# 12__MOT_tCONNECTOR.net
KiCad netlist of a schematic drawn in Altium Designer
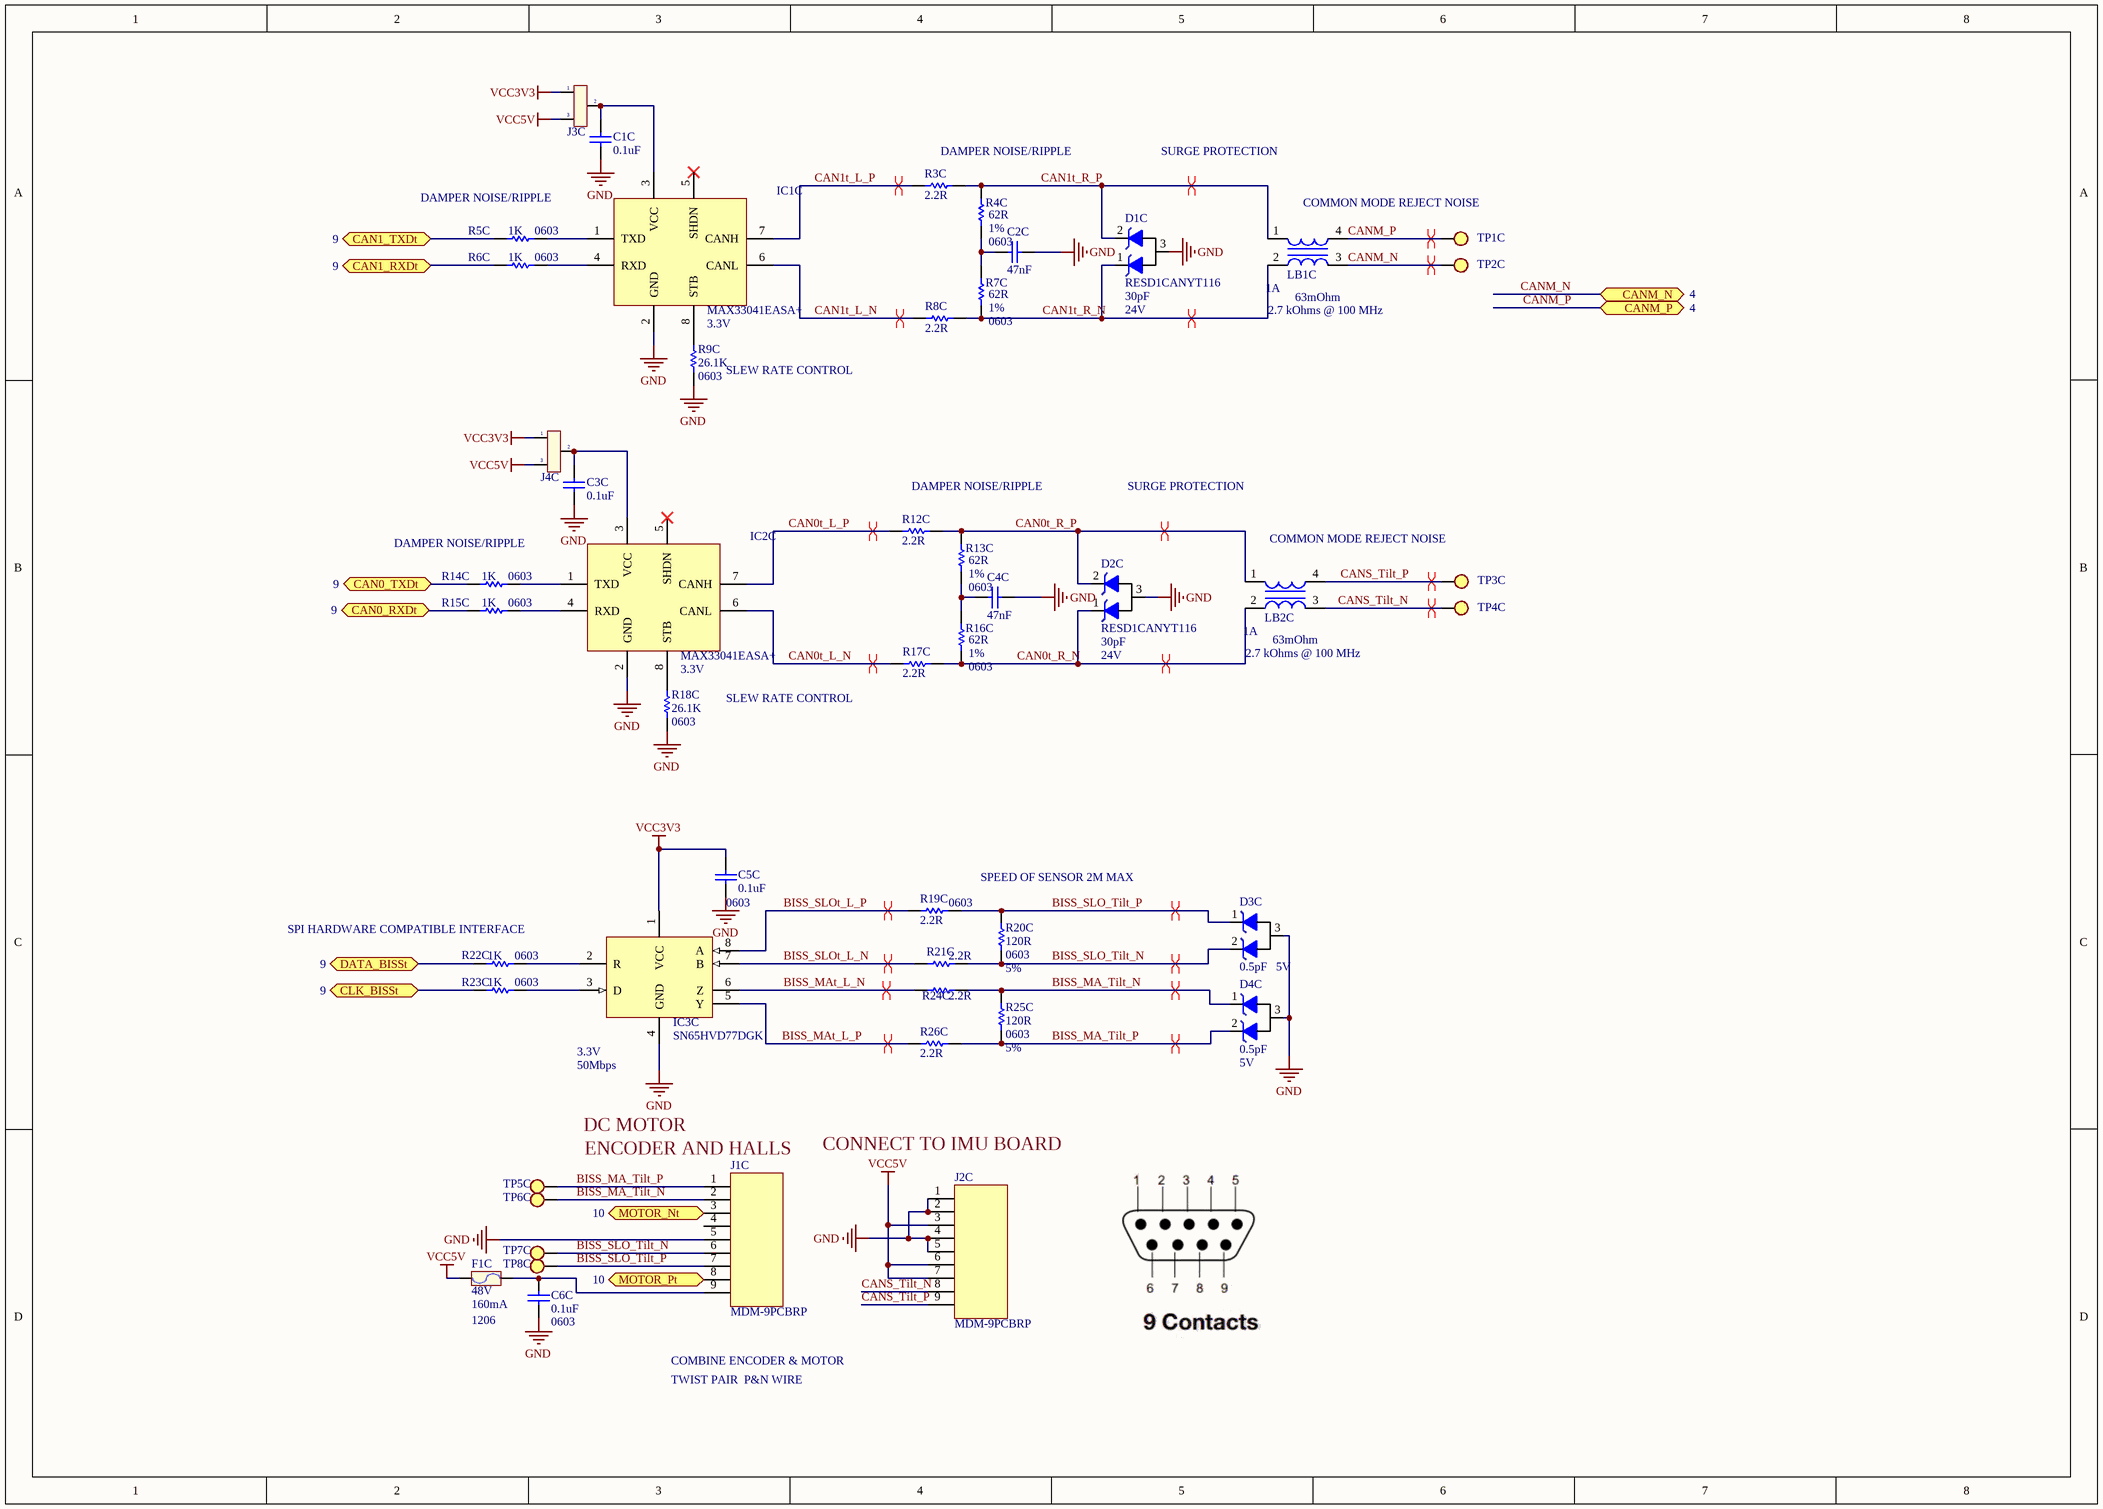
[diagram p0: [12]_MOT_tCONNECTOR.SchDoc]

(export (version "E")
  (design (tool "Eeschema 10.0.6"))
  (components
    (comp (ref "C1C")
      (value "0.1uF")
      (footprint "CAP 0603")
      (description "CAP-CER,SMD;0.1UF,10%,50V,X7R,0603")
      (fields (field (name "VOLTAGE") "50V") (field (name "TOLERANCE") "±10%"))
      (libsource (lib "Slider") (part "Cap"))
    )
    (comp (ref "C2C")
      (value "47nF")
      (footprint "CAP 0603")
      (description "CAP-CER,SMD; 47nF,10%,50V,X7R,0603")
      (fields (field (name "VOLTAGE") "50V") (field (name "TOLERANCE") "±10%"))
      (libsource (lib "Slider") (part "Cap"))
    )
    (comp (ref "C3C")
      (value "0.1uF")
      (footprint "CAP 0603")
      (description "CAP-CER,SMD;0.1UF,10%,50V,X7R,0603")
      (fields (field (name "VOLTAGE") "50V") (field (name "TOLERANCE") "±10%"))
      (libsource (lib "Slider") (part "Cap"))
    )
    (comp (ref "C4C")
      (value "47nF")
      (footprint "CAP 0603")
      (description "CAP-CER,SMD; 47nF,10%,50V,X7R,0603")
      (fields (field (name "VOLTAGE") "50V") (field (name "TOLERANCE") "±10%"))
      (libsource (lib "Slider") (part "Cap"))
    )
    (comp (ref "C5C")
      (value "0.1uF")
      (footprint "0603")
      (description "CAP-CER,SMD;0.1UF,10%,50V,X7R,0603")
      (fields (field (name "VOLTAGE") "50V") (field (name "TOLERANCE") "±10%"))
      (libsource (lib "Slider") (part "Cap"))
    )
    (comp (ref "C6C")
      (value "0.1uF")
      (footprint "0603")
      (description "CAP-CER,SMD;0.1UF,10%,50V,X7R,0603")
      (fields (field (name "VOLTAGE") "50V") (field (name "TOLERANCE") "±10%"))
      (libsource (lib "Slider") (part "Cap"))
    )
    (comp (ref "D1C")
      (value "RESD1CANYT116")
      (footprint "SOT-23-3")
      (description "TVS DIODE 24VWM 50VC SOT23-")
      (fields
        (field (name "POWER") "230W")
        (field (name "CAPACITANCE") "30pF")
        (field (name "VOLTAGE") "24V")
      )
      (libsource (lib "") (part "TVS_DUAL_SIGNAL_5V_SOT23_1"))
    )
    (comp (ref "D2C")
      (value "RESD1CANYT116")
      (footprint "SOT-23-3")
      (description "TVS DIODE 24VWM 50VC SOT23-")
      (fields
        (field (name "POWER") "230W")
        (field (name "CAPACITANCE") "30pF")
        (field (name "VOLTAGE") "24V")
      )
      (libsource (lib "") (part "TVS_DUAL_SIGNAL_5V_SOT23_1"))
    )
    (comp (ref "D3C")
      (value "ESDR0502BT1G")
      (footprint "SOT-416")
      (description "5V, ESD PROTECTION DEVICES, SOT-23")
      (fields
        (field (name "MANUFACTURER2_PART#") "DF3D6.8MS,LF")
        (field (name "POWER") "320W")
        (field (name "CAPACITANCE") "0.5pF")
        (field (name "VOLTAGE") "5V")
      )
      (libsource (lib "My Library") (part "TVS_DUAL_SIGNAL_5V_SOT23"))
    )
    (comp (ref "D4C")
      (value "ESDR0502BT1G")
      (footprint "SOT-416")
      (description "5V, ESD PROTECTION DEVICES, SOT-23")
      (fields
        (field (name "MANUFACTURER2_PART#") "DF3D6.8MS,LF")
        (field (name "POWER") "320W")
        (field (name "CAPACITANCE") "0.5pF")
        (field (name "VOLTAGE") "5V")
      )
      (libsource (lib "My Library") (part "TVS_DUAL_SIGNAL_5V_SOT23"))
    )
    (comp (ref "F1C")
      (value "0ZCG0014FF2C")
      (footprint "RES 1206")
      (description "PTC RESET FUSE 48V 160MA 1206")
      (fields
        (field (name "MANUFACTURER1_PART#") "0ZCJ0016FF2E")
        (field (name "MANUFACTURER2_PART#") "CLA1684")
        (field (name "VOLTAGE - RATED") "48V")
        (field (name "PACKAGE / CASE") "1206")
        (field (name "CURRENT RATING (AMPS)") "160mA")
      )
      (libsource (lib "K Shematic") (part "0875.800MXEP"))
    )
    (comp (ref "IC1C")
      (value "MAX33041EASA+")
      (footprint "8-SOIC")
      (description "IC CAN TXRX 3.3V 2MBPS SOIC")
      (fields (field (name "MANUFACTURER PART NUMBER") "MAX33041EASA+") (field (name "VOLTAGE") "3.3V"))
      (libsource (lib "OE Seeker-IsolatedPower") (part "IC;IC CAN TRANSEIVER HS,8SOIC,-40TO150°C,TJA1042T/3,118"))
    )
    (comp (ref "IC2C")
      (value "MAX33041EASA+")
      (footprint "8-SOIC")
      (description "IC CAN TXRX 3.3V 2MBPS SOIC")
      (fields (field (name "MANUFACTURER PART NUMBER") "MAX33041EASA+") (field (name "VOLTAGE") "3.3V"))
      (libsource (lib "OE Seeker-IsolatedPower") (part "IC;IC CAN TRANSEIVER HS,8SOIC,-40TO150°C,TJA1042T/3,118"))
    )
    (comp (ref "IC3C")
      (value "IC;IC TRANSCEIVER FULL 1/1 8SOIC,8-SOIC,-40TO 85°C,SN65HVD77DR")
      (footprint "8-VSSOP")
      (description "IC TRANSCEIVER FULL 1/1 8VSSOP")
      (fields
        (field (name "MANUFACTURER") "TI")
        (field (name "MANUFACTURER PART NUMBER") "SN65HVD77DGK")
        (field (name "MANUFACTURER1_PART#") "SN65HVD77DGK")
        (field (name "VOLTAGE") "3.3V")
        (field (name "SPEED") "50Mbps")
      )
      (libsource (lib "DRIVER MOTION TILT_NEW") (part "IC;IC TRANSCEIVER FULL 1/1 8SOIC,8-SOIC,-40TO 85°C,SN65HVD77DR"))
    )
    (comp (ref "J1C")
      (value "CONN-DIP;CONN MICRO-D PLUG 9POS R/A SLDR,M,MDM-9PCBRP")
      (footprint "MDM-9PCBRP")
      (description "CONN MICRO-D PLUG 9POS R/A SLDR")
      (fields
        (field (name "MANUFACTURER") "ITT CANNON, LLC")
        (field (name "MANUFACTURER PART NUMBER") "MDM-9PCBRP")
        (field (name "MANUFACTURER1_PART#") "MDM-9PCBRP")
      )
      (libsource (lib "DRIVER MOTION PAN_NEW") (part "CONN-DIP;CONN MICRO-D PLUG 9POS R/A SLDR,M,MDM-9PCBRP"))
    )
    (comp (ref "J2C")
      (value "CONN-DIP;CONN MICRO-D PLUG 9POS R/A SLDR,M,MDM-9PCBRP")
      (footprint "MDM-9PCBRP")
      (description "CONN MICRO-D PLUG 9POS R/A SLDR")
      (fields
        (field (name "MANUFACTURER") "ITT CANNON, LLC")
        (field (name "MANUFACTURER PART NUMBER") "MDM-9PCBRP")
        (field (name "MANUFACTURER1_PART#") "MDM-9PCBRP")
      )
      (libsource (lib "IMU_NEW") (part "CONN-DIP;CONN MICRO-D PLUG 9POS R/A SLDR,M,MDM-9PCBRP"))
    )
    (comp (ref "J3C")
      (value "JP 2-1")
      (footprint "JP3")
      (description "Jumper 2-1")
      (libsource (lib "ThanhSchematicLib") (part "JP 2-1"))
    )
    (comp (ref "J4C")
      (value "JP 2-1")
      (footprint "JP3")
      (description "Jumper 2-1")
      (libsource (lib "ThanhSchematicLib") (part "JP 2-1"))
    )
    (comp (ref "LB1C")
      (value "MCM-7060M-272-RU")
      (footprint "MCM-7060M")
      (description "CMC 1A 2LN 2.7KOHM SMD")
      (fields
        (field (name "CURRENT") "1A")
        (field (name "IMPEDANCE") "2.7 kOhms @ 100 MHz")
        (field (name "DCR") "63mOhm")
      )
      (libsource (lib "OE Seeker-IsolatedPower") (part "CHOKE-SMD;90OHM@100MHz,0.15A,5V,DLP11SA900HL2L"))
    )
    (comp (ref "LB2C")
      (value "MCM-7060M-272-RU")
      (footprint "MCM-7060M")
      (description "CMC 1A 2LN 2.7KOHM SMD")
      (fields
        (field (name "CURRENT") "1A")
        (field (name "IMPEDANCE") "2.7 kOhms @ 100 MHz")
        (field (name "DCR") "63mOhm")
      )
      (libsource (lib "OE Seeker-IsolatedPower") (part "CHOKE-SMD;90OHM@100MHz,0.15A,5V,DLP11SA900HL2L"))
    )
    (comp (ref "R3C")
      (value "2.2R")
      (footprint "res 0603")
      (description "RES SMD 2.2 OHM 5% 1/10W 0603")
      (fields
        (field (name "MANUFACTURER1_PART#") "RC0603JR-072R2L")
        (field (name "MANUFACTURER2_PART#") "RMCF0603JT2R20")
      )
      (libsource (lib "Full") (part "Res0.3"))
    )
    (comp (ref "R4C")
      (value "62R")
      (footprint "R0603")
      (description "RES SM 62 OHM 1% 1/10W 0603")
      (fields
        (field (name "MANUFACTURER1_PART#") "RMCF0603FT62R0")
        (field (name "MANUFACTURER2_PART#") "RC0603FR-0762RL")
        (field (name "TOLERANCE") "1%")
        (field (name "PACKAGE") "0603")
      )
      (libsource (lib "OE Seeker-IsolatedPower") (part "RES-SMD;60.4OHM,1%,0402,1/10W"))
    )
    (comp (ref "R5C")
      (value "1K")
      (footprint "res 0603")
      (description "RES SMD,1K OHM,5%,1/10W,0603")
      (fields
        (field (name "MANUFACTURER1_PART#") "RMCF06031K00JNEAC")
        (field (name "MANUFACTURER2_PART#") "R0603J1KTG")
        (field (name "PCB FOOTPRINT") "0603")
      )
      (libsource (lib "Full") (part "Res0.3"))
    )
    (comp (ref "R6C")
      (value "1K")
      (footprint "res 0603")
      (description "RES SMD,1K OHM,5%,1/10W,0603")
      (fields
        (field (name "MANUFACTURER1_PART#") "RMCF06031K00JNEAC")
        (field (name "MANUFACTURER2_PART#") "R0603J1KTG")
        (field (name "PCB FOOTPRINT") "0603")
      )
      (libsource (lib "Full") (part "Res0.3"))
    )
    (comp (ref "R7C")
      (value "62R")
      (footprint "R0603")
      (description "RES SM 62 OHM 1% 1/10W 0603")
      (fields
        (field (name "MANUFACTURER1_PART#") "RMCF0603FT62R0")
        (field (name "MANUFACTURER2_PART#") "RC0603FR-0762RL")
        (field (name "TOLERANCE") "1%")
        (field (name "PACKAGE") "0603")
      )
      (libsource (lib "OE Seeker-IsolatedPower") (part "RES-SMD;60.4OHM,1%,0402,1/10W"))
    )
    (comp (ref "R8C")
      (value "2.2R")
      (footprint "res 0603")
      (description "RES SMD 2.2 OHM 5% 1/10W 0603")
      (fields
        (field (name "MANUFACTURER1_PART#") "RC0603JR-072R2L")
        (field (name "MANUFACTURER2_PART#") "RMCF0603JT2R20")
      )
      (libsource (lib "Full") (part "Res0.3"))
    )
    (comp (ref "R9C")
      (value "26.1K")
      (footprint "R0603")
      (description "RES 26.1K OHM 1% 1/10W 0603")
      (fields
        (field (name "MANUFACTURER1_PART#") "RMCF0603FT26K1")
        (field (name "MANUFACTURER2_PART#") "RC0603FR-0726K1L")
        (field (name "PCB FOOTPRINT") "0603")
      )
      (libsource (lib "altium-import") (part "root_3_Res0.3_"))
    )
    (comp (ref "R12C")
      (value "2.2R")
      (footprint "res 0603")
      (description "RES SMD 2.2 OHM 5% 1/10W 0603")
      (fields
        (field (name "MANUFACTURER1_PART#") "RC0603JR-072R2L")
        (field (name "MANUFACTURER2_PART#") "RMCF0603JT2R20")
      )
      (libsource (lib "Full") (part "Res0.3"))
    )
    (comp (ref "R13C")
      (value "62R")
      (footprint "R0603")
      (description "RES SM 62 OHM 1% 1/10W 0603")
      (fields
        (field (name "MANUFACTURER1_PART#") "RMCF0603FT62R0")
        (field (name "MANUFACTURER2_PART#") "RC0603FR-0762RL")
        (field (name "TOLERANCE") "1%")
        (field (name "PACKAGE") "0603")
      )
      (libsource (lib "OE Seeker-IsolatedPower") (part "RES-SMD;60.4OHM,1%,0402,1/10W"))
    )
    (comp (ref "R14C")
      (value "1K")
      (footprint "res 0603")
      (description "RES SMD,1K OHM,5%,1/10W,0603")
      (fields
        (field (name "MANUFACTURER1_PART#") "RMCF06031K00JNEAC")
        (field (name "MANUFACTURER2_PART#") "R0603J1KTG")
        (field (name "PCB FOOTPRINT") "0603")
      )
      (libsource (lib "Full") (part "Res0.3"))
    )
    (comp (ref "R15C")
      (value "1K")
      (footprint "res 0603")
      (description "RES SMD,1K OHM,5%,1/10W,0603")
      (fields
        (field (name "MANUFACTURER1_PART#") "RMCF06031K00JNEAC")
        (field (name "MANUFACTURER2_PART#") "R0603J1KTG")
        (field (name "PCB FOOTPRINT") "0603")
      )
      (libsource (lib "Full") (part "Res0.3"))
    )
    (comp (ref "R16C")
      (value "62R")
      (footprint "R0603")
      (description "RES SM 62 OHM 1% 1/10W 0603")
      (fields
        (field (name "MANUFACTURER1_PART#") "RMCF0603FT62R0")
        (field (name "MANUFACTURER2_PART#") "RC0603FR-0762RL")
        (field (name "TOLERANCE") "1%")
        (field (name "PACKAGE") "0603")
      )
      (libsource (lib "OE Seeker-IsolatedPower") (part "RES-SMD;60.4OHM,1%,0402,1/10W"))
    )
    (comp (ref "R17C")
      (value "2.2R")
      (footprint "res 0603")
      (description "RES SMD 2.2 OHM 5% 1/10W 0603")
      (fields
        (field (name "MANUFACTURER1_PART#") "RC0603JR-072R2L")
        (field (name "MANUFACTURER2_PART#") "RMCF0603JT2R20")
      )
      (libsource (lib "Full") (part "Res0.3"))
    )
    (comp (ref "R18C")
      (value "26.1K")
      (footprint "R0603")
      (description "RES 26.1K OHM 1% 1/10W 0603")
      (fields
        (field (name "MANUFACTURER1_PART#") "RMCF0603FT26K1")
        (field (name "MANUFACTURER2_PART#") "RC0603FR-0726K1L")
        (field (name "PCB FOOTPRINT") "0603")
      )
      (libsource (lib "altium-import") (part "root_3_Res0.3_"))
    )
    (comp (ref "R19C")
      (value "2.2R")
      (footprint "res 0603")
      (description "RES SMD 2.2 OHM 5% 1/10W 0603")
      (fields
        (field (name "MANUFACTURER1_PART#") "RC0603JR-072R2L")
        (field (name "MANUFACTURER2_PART#") "RMCF0603JT2R20")
        (field (name "PCB FOOTPRINT") "0603")
      )
      (libsource (lib "Full") (part "Res0.3"))
    )
    (comp (ref "R20C")
      (value "120R")
      (footprint "res 0603")
      (description "RES 120 OHM 5% 1/10W 0603")
      (fields
        (field (name "MANUFACTURER1_PART#") "RMCF0603JG120R")
        (field (name "PCB_ FOOTPRINT") "0603")
        (field (name "TOLERANCE") "5%")
      )
      (libsource (lib "thuvien") (part "RES 120 OHM 5% 1/10W 0603"))
    )
    (comp (ref "R21C")
      (value "2.2R")
      (footprint "res 0603")
      (description "RES SMD 2.2 OHM 5% 1/10W 0603")
      (fields
        (field (name "MANUFACTURER1_PART#") "RC0603JR-072R2L")
        (field (name "MANUFACTURER2_PART#") "RMCF0603JT2R20")
      )
      (libsource (lib "Full") (part "Res0.3"))
    )
    (comp (ref "R22C")
      (value "1K")
      (footprint "res 0603")
      (description "RES SMD,1K OHM,5%,1/10W,0603")
      (fields
        (field (name "MANUFACTURER1_PART#") "RMCF06031K00JNEAC")
        (field (name "MANUFACTURER2_PART#") "R0603J1KTG")
        (field (name "PCB FOOTPRINT") "0603")
      )
      (libsource (lib "Full") (part "Res0.3"))
    )
    (comp (ref "R23C")
      (value "1K")
      (footprint "res 0603")
      (description "RES SMD,1K OHM,5%,1/10W,0603")
      (fields
        (field (name "MANUFACTURER1_PART#") "RMCF06031K00JNEAC")
        (field (name "MANUFACTURER2_PART#") "R0603J1KTG")
        (field (name "PCB FOOTPRINT") "0603")
      )
      (libsource (lib "Full") (part "Res0.3"))
    )
    (comp (ref "R24C")
      (value "2.2R")
      (footprint "res 0603")
      (description "RES SMD 2.2 OHM 5% 1/10W 0603")
      (fields
        (field (name "MANUFACTURER1_PART#") "RC0603JR-072R2L")
        (field (name "MANUFACTURER2_PART#") "RMCF0603JT2R20")
      )
      (libsource (lib "Full") (part "Res0.3"))
    )
    (comp (ref "R25C")
      (value "120R")
      (footprint "res 0603")
      (description "RES 120 OHM 5% 1/10W 0603")
      (fields
        (field (name "MANUFACTURER1_PART#") "RMCF0603JG120R")
        (field (name "PCB_ FOOTPRINT") "0603")
        (field (name "TOLERANCE") "5%")
      )
      (libsource (lib "thuvien") (part "RES 120 OHM 5% 1/10W 0603"))
    )
    (comp (ref "R26C")
      (value "2.2R")
      (footprint "res 0603")
      (description "RES SMD 2.2 OHM 5% 1/10W 0603")
      (fields
        (field (name "MANUFACTURER1_PART#") "RC0603JR-072R2L")
        (field (name "MANUFACTURER2_PART#") "RMCF0603JT2R20")
      )
      (libsource (lib "Full") (part "Res0.3"))
    )
    (comp (ref "TP1C")
      (value "TP SMD")
      (footprint "TESTPOINT")
      (description "TEST POINT")
      (libsource (lib "VSM") (part "TP SMD"))
    )
    (comp (ref "TP2C")
      (value "TP SMD")
      (footprint "TESTPOINT")
      (description "TEST POINT")
      (libsource (lib "VSM") (part "TP SMD"))
    )
    (comp (ref "TP3C")
      (value "TP SMD")
      (footprint "TESTPOINT")
      (description "TEST POINT")
      (libsource (lib "VSM") (part "TP SMD"))
    )
    (comp (ref "TP4C")
      (value "TP SMD")
      (footprint "TESTPOINT")
      (description "TEST POINT")
      (libsource (lib "VSM") (part "TP SMD"))
    )
    (comp (ref "TP5C")
      (value "TP SMD")
      (footprint "TESTPOINT")
      (description "TEST POINT")
      (libsource (lib "VSM") (part "TP SMD"))
    )
    (comp (ref "TP6C")
      (value "TP SMD")
      (footprint "TESTPOINT")
      (description "TEST POINT")
      (libsource (lib "VSM") (part "TP SMD"))
    )
    (comp (ref "TP7C")
      (value "TP SMD")
      (footprint "TESTPOINT")
      (description "TEST POINT")
      (libsource (lib "VSM") (part "TP SMD"))
    )
    (comp (ref "TP8C")
      (value "TP SMD")
      (footprint "TESTPOINT")
      (description "TEST POINT")
      (libsource (lib "VSM") (part "TP SMD"))
    )
  )
  (nets
    (net (code "1") (name "/BISS_MA_Tilt_N") (class "Default")
      (node (ref "D4C") (pin "1") (pinfunction "K_1") (pintype "passive"))
      (node (ref "J1C") (pin "2") (pinfunction "2_2") (pintype "passive"))
      (node (ref "R24C") (pin "1") (pinfunction "1_1") (pintype "passive"))
      (node (ref "R25C") (pin "1") (pinfunction "1_1") (pintype "passive"))
      (node (ref "TP6C") (pin "1") (pinfunction "1_1") (pintype "passive"))
    )
    (net (code "2") (name "/BISS_MA_Tilt_P") (class "Default")
      (node (ref "D4C") (pin "2") (pinfunction "K_2") (pintype "passive"))
      (node (ref "J1C") (pin "1") (pinfunction "1_1") (pintype "passive"))
      (node (ref "R25C") (pin "2") (pinfunction "2_2") (pintype "passive"))
      (node (ref "R26C") (pin "1") (pinfunction "1_1") (pintype "passive"))
      (node (ref "TP5C") (pin "1") (pinfunction "1_1") (pintype "passive"))
    )
    (net (code "3") (name "/BISS_MAt_L_N") (class "Default")
      (node (ref "IC3C") (pin "6") (pinfunction "Z_6") (pintype "passive"))
      (node (ref "R24C") (pin "2") (pinfunction "2_2") (pintype "passive"))
    )
    (net (code "4") (name "/BISS_MAt_L_P") (class "Default")
      (node (ref "IC3C") (pin "5") (pinfunction "Y_5") (pintype "passive"))
      (node (ref "R26C") (pin "2") (pinfunction "2_2") (pintype "passive"))
    )
    (net (code "5") (name "/BISS_SLO_Tilt_N") (class "Default")
      (node (ref "D3C") (pin "2") (pinfunction "K_2") (pintype "passive"))
      (node (ref "J1C") (pin "6") (pinfunction "6_6") (pintype "passive"))
      (node (ref "R20C") (pin "2") (pinfunction "2_2") (pintype "passive"))
      (node (ref "R21C") (pin "1") (pinfunction "1_1") (pintype "passive"))
      (node (ref "TP7C") (pin "1") (pinfunction "1_1") (pintype "passive"))
    )
    (net (code "6") (name "/BISS_SLO_Tilt_P") (class "Default")
      (node (ref "D3C") (pin "1") (pinfunction "K_1") (pintype "passive"))
      (node (ref "J1C") (pin "7") (pinfunction "7_7") (pintype "passive"))
      (node (ref "R19C") (pin "1") (pinfunction "1_1") (pintype "passive"))
      (node (ref "R20C") (pin "1") (pinfunction "1_1") (pintype "passive"))
      (node (ref "TP8C") (pin "1") (pinfunction "1_1") (pintype "passive"))
    )
    (net (code "7") (name "/BISS_SLOt_L_N") (class "Default")
      (node (ref "IC3C") (pin "7") (pinfunction "B_7") (pintype "input"))
      (node (ref "R21C") (pin "2") (pinfunction "2_2") (pintype "passive"))
    )
    (net (code "8") (name "/BISS_SLOt_L_P") (class "Default")
      (node (ref "IC3C") (pin "8") (pinfunction "A_8") (pintype "input"))
      (node (ref "R19C") (pin "2") (pinfunction "2_2") (pintype "passive"))
    )
    (net (code "9") (name "/CAN0_RXDt") (class "Default")
      (node (ref "R15C") (pin "2") (pinfunction "2_2") (pintype "passive"))
    )
    (net (code "10") (name "/CAN0_TXDt") (class "Default")
      (node (ref "R14C") (pin "2") (pinfunction "2_2") (pintype "passive"))
    )
    (net (code "11") (name "/CAN0t_L_N") (class "Default")
      (node (ref "IC2C") (pin "6") (pinfunction "CANL_6") (pintype "passive"))
      (node (ref "R17C") (pin "2") (pinfunction "2_2") (pintype "passive"))
    )
    (net (code "12") (name "/CAN0t_L_P") (class "Default")
      (node (ref "IC2C") (pin "7") (pinfunction "CANH_7") (pintype "passive"))
      (node (ref "R12C") (pin "2") (pinfunction "2_2") (pintype "passive"))
    )
    (net (code "13") (name "/CAN0t_R_N") (class "Default")
      (node (ref "D2C") (pin "1") (pinfunction "K_1") (pintype "passive"))
      (node (ref "LB2C") (pin "2") (pinfunction "2_2") (pintype "passive"))
      (node (ref "R16C") (pin "1") (pinfunction "1_1") (pintype "passive"))
      (node (ref "R17C") (pin "1") (pinfunction "1_1") (pintype "passive"))
    )
    (net (code "14") (name "/CAN0t_R_P") (class "Default")
      (node (ref "D2C") (pin "2") (pinfunction "K_2") (pintype "passive"))
      (node (ref "LB2C") (pin "1") (pinfunction "1_1") (pintype "passive"))
      (node (ref "R12C") (pin "1") (pinfunction "1_1") (pintype "passive"))
      (node (ref "R13C") (pin "2") (pinfunction "2_2") (pintype "passive"))
    )
    (net (code "15") (name "/CAN1_RXDt") (class "Default")
      (node (ref "R6C") (pin "2") (pinfunction "2_2") (pintype "passive"))
    )
    (net (code "16") (name "/CAN1_TXDt") (class "Default")
      (node (ref "R5C") (pin "2") (pinfunction "2_2") (pintype "passive"))
    )
    (net (code "17") (name "/CAN1t_L_N") (class "Default")
      (node (ref "IC1C") (pin "6") (pinfunction "CANL_6") (pintype "passive"))
      (node (ref "R8C") (pin "2") (pinfunction "2_2") (pintype "passive"))
    )
    (net (code "18") (name "/CAN1t_L_P") (class "Default")
      (node (ref "IC1C") (pin "7") (pinfunction "CANH_7") (pintype "passive"))
      (node (ref "R3C") (pin "2") (pinfunction "2_2") (pintype "passive"))
    )
    (net (code "19") (name "/CAN1t_R_N") (class "Default")
      (node (ref "D1C") (pin "1") (pinfunction "K_1") (pintype "passive"))
      (node (ref "LB1C") (pin "2") (pinfunction "2_2") (pintype "passive"))
      (node (ref "R7C") (pin "1") (pinfunction "1_1") (pintype "passive"))
      (node (ref "R8C") (pin "1") (pinfunction "1_1") (pintype "passive"))
    )
    (net (code "20") (name "/CAN1t_R_P") (class "Default")
      (node (ref "D1C") (pin "2") (pinfunction "K_2") (pintype "passive"))
      (node (ref "LB1C") (pin "1") (pinfunction "1_1") (pintype "passive"))
      (node (ref "R3C") (pin "1") (pinfunction "1_1") (pintype "passive"))
      (node (ref "R4C") (pin "2") (pinfunction "2_2") (pintype "passive"))
    )
    (net (code "21") (name "/CANM_N") (class "Default")
      (node (ref "LB1C") (pin "3") (pinfunction "3_3") (pintype "passive"))
      (node (ref "TP2C") (pin "1") (pinfunction "1_1") (pintype "passive"))
    )
    (net (code "22") (name "/CANM_P") (class "Default")
      (node (ref "LB1C") (pin "4") (pinfunction "4_4") (pintype "passive"))
      (node (ref "TP1C") (pin "1") (pinfunction "1_1") (pintype "passive"))
    )
    (net (code "23") (name "/CANS_Tilt_N") (class "Default")
      (node (ref "J2C") (pin "8") (pinfunction "8_8") (pintype "passive"))
      (node (ref "LB2C") (pin "3") (pinfunction "3_3") (pintype "passive"))
      (node (ref "TP4C") (pin "1") (pinfunction "1_1") (pintype "passive"))
    )
    (net (code "24") (name "/CANS_Tilt_P") (class "Default")
      (node (ref "J2C") (pin "9") (pinfunction "9_9") (pintype "passive"))
      (node (ref "LB2C") (pin "4") (pinfunction "4_4") (pintype "passive"))
      (node (ref "TP3C") (pin "1") (pinfunction "1_1") (pintype "passive"))
    )
    (net (code "25") (name "/CLK_BISSt") (class "Default")
      (node (ref "R23C") (pin "2") (pinfunction "2_2") (pintype "passive"))
    )
    (net (code "26") (name "/DATA_BISSt") (class "Default")
      (node (ref "R22C") (pin "2") (pinfunction "2_2") (pintype "passive"))
    )
    (net (code "27") (name "/MOTOR_Nt") (class "Default")
      (node (ref "J1C") (pin "3") (pinfunction "3_3") (pintype "passive"))
    )
    (net (code "28") (name "/MOTOR_Pt") (class "Default")
      (node (ref "J1C") (pin "8") (pinfunction "8_8") (pintype "passive"))
    )
    (net (code "29") (name "GND") (class "Default")
      (node (ref "C1C") (pin "2") (pinfunction "2_2") (pintype "passive"))
      (node (ref "C2C") (pin "2") (pinfunction "2_2") (pintype "passive"))
      (node (ref "C3C") (pin "2") (pinfunction "2_2") (pintype "passive"))
      (node (ref "C4C") (pin "2") (pinfunction "2_2") (pintype "passive"))
      (node (ref "C5C") (pin "2") (pinfunction "2_2") (pintype "passive"))
      (node (ref "C6C") (pin "2") (pinfunction "2_2") (pintype "passive"))
      (node (ref "D1C") (pin "3") (pinfunction "A_3") (pintype "passive"))
      (node (ref "D2C") (pin "3") (pinfunction "A_3") (pintype "passive"))
      (node (ref "D3C") (pin "3") (pinfunction "A_3") (pintype "passive"))
      (node (ref "D4C") (pin "3") (pinfunction "A_3") (pintype "passive"))
      (node (ref "IC1C") (pin "2") (pinfunction "GND_2") (pintype "passive"))
      (node (ref "IC2C") (pin "2") (pinfunction "GND_2") (pintype "passive"))
      (node (ref "IC3C") (pin "4") (pinfunction "GND_4") (pintype "passive"))
      (node (ref "J1C") (pin "5") (pinfunction "5_5") (pintype "passive"))
      (node (ref "J2C") (pin "1") (pinfunction "1_1") (pintype "passive"))
      (node (ref "J2C") (pin "2") (pinfunction "2_2") (pintype "passive"))
      (node (ref "J2C") (pin "4") (pinfunction "4_4") (pintype "passive"))
      (node (ref "J2C") (pin "5") (pinfunction "5_5") (pintype "passive"))
      (node (ref "R18C") (pin "2") (pinfunction "2_2") (pintype "passive"))
      (node (ref "R9C") (pin "2") (pinfunction "2_2") (pintype "passive"))
    )
    (net (code "30") (name "Net-(C2C-Pad1)") (class "Default")
      (node (ref "C2C") (pin "1") (pinfunction "1_1") (pintype "passive"))
      (node (ref "R4C") (pin "1") (pinfunction "1_1") (pintype "passive"))
      (node (ref "R7C") (pin "2") (pinfunction "2_2") (pintype "passive"))
    )
    (net (code "31") (name "Net-(C4C-Pad1)") (class "Default")
      (node (ref "C4C") (pin "1") (pinfunction "1_1") (pintype "passive"))
      (node (ref "R13C") (pin "1") (pinfunction "1_1") (pintype "passive"))
      (node (ref "R16C") (pin "2") (pinfunction "2_2") (pintype "passive"))
    )
    (net (code "32") (name "Net-(C6C-Pad1)") (class "Default")
      (node (ref "C6C") (pin "1") (pinfunction "1_1") (pintype "passive"))
      (node (ref "F1C") (pin "1") (pinfunction "1_1") (pintype "passive"))
      (node (ref "J1C") (pin "9") (pinfunction "9_9") (pintype "passive"))
    )
    (net (code "33") (name "Net-(IC1C-RXD)") (class "Default")
      (node (ref "IC1C") (pin "4") (pinfunction "RXD_4") (pintype "passive"))
      (node (ref "R6C") (pin "1") (pinfunction "1_1") (pintype "passive"))
    )
    (net (code "34") (name "Net-(IC1C-STB)") (class "Default")
      (node (ref "IC1C") (pin "8") (pinfunction "STB_8") (pintype "passive"))
      (node (ref "R9C") (pin "1") (pinfunction "1_1") (pintype "passive"))
    )
    (net (code "35") (name "Net-(IC1C-TXD)") (class "Default")
      (node (ref "IC1C") (pin "1") (pinfunction "TXD_1") (pintype "passive"))
      (node (ref "R5C") (pin "1") (pinfunction "1_1") (pintype "passive"))
    )
    (net (code "36") (name "Net-(IC1C-VCC)") (class "Default")
      (node (ref "C1C") (pin "1") (pinfunction "1_1") (pintype "passive"))
      (node (ref "IC1C") (pin "3") (pinfunction "VCC_3") (pintype "passive"))
      (node (ref "J3C") (pin "2") (pinfunction "2_2") (pintype "passive"))
    )
    (net (code "37") (name "Net-(IC2C-RXD)") (class "Default")
      (node (ref "IC2C") (pin "4") (pinfunction "RXD_4") (pintype "passive"))
      (node (ref "R15C") (pin "1") (pinfunction "1_1") (pintype "passive"))
    )
    (net (code "38") (name "Net-(IC2C-STB)") (class "Default")
      (node (ref "IC2C") (pin "8") (pinfunction "STB_8") (pintype "passive"))
      (node (ref "R18C") (pin "1") (pinfunction "1_1") (pintype "passive"))
    )
    (net (code "39") (name "Net-(IC2C-TXD)") (class "Default")
      (node (ref "IC2C") (pin "1") (pinfunction "TXD_1") (pintype "passive"))
      (node (ref "R14C") (pin "1") (pinfunction "1_1") (pintype "passive"))
    )
    (net (code "40") (name "Net-(IC2C-VCC)") (class "Default")
      (node (ref "C3C") (pin "1") (pinfunction "1_1") (pintype "passive"))
      (node (ref "IC2C") (pin "3") (pinfunction "VCC_3") (pintype "passive"))
      (node (ref "J4C") (pin "2") (pinfunction "2_2") (pintype "passive"))
    )
    (net (code "41") (name "Net-(IC3C-D)") (class "Default")
      (node (ref "IC3C") (pin "3") (pinfunction "D_3") (pintype "input"))
      (node (ref "R23C") (pin "1") (pinfunction "1_1") (pintype "passive"))
    )
    (net (code "42") (name "Net-(IC3C-R)") (class "Default")
      (node (ref "IC3C") (pin "2") (pinfunction "R_2") (pintype "passive"))
      (node (ref "R22C") (pin "1") (pinfunction "1_1") (pintype "passive"))
    )
    (net (code "43") (name "VCC3V3") (class "Default")
      (node (ref "C5C") (pin "1") (pinfunction "1_1") (pintype "passive"))
      (node (ref "IC3C") (pin "1") (pinfunction "VCC_1") (pintype "passive"))
      (node (ref "J3C") (pin "1") (pinfunction "1_1") (pintype "passive"))
      (node (ref "J4C") (pin "1") (pinfunction "1_1") (pintype "passive"))
    )
    (net (code "44") (name "VCC5V") (class "Default")
      (node (ref "F1C") (pin "2") (pinfunction "2_2") (pintype "passive"))
      (node (ref "J2C") (pin "3") (pinfunction "3_3") (pintype "passive"))
      (node (ref "J2C") (pin "6") (pinfunction "6_6") (pintype "passive"))
      (node (ref "J2C") (pin "7") (pinfunction "7_7") (pintype "passive"))
      (node (ref "J3C") (pin "3") (pinfunction "3_3") (pintype "passive"))
      (node (ref "J4C") (pin "3") (pinfunction "3_3") (pintype "passive"))
    )
    (net (code "45") (name "unconnected-(IC1C-SHDN-Pad5)") (class "Default")
      (node (ref "IC1C") (pin "5") (pinfunction "SHDN_5") (pintype "passive+no_connect"))
    )
    (net (code "46") (name "unconnected-(IC2C-SHDN-Pad5)") (class "Default")
      (node (ref "IC2C") (pin "5") (pinfunction "SHDN_5") (pintype "passive+no_connect"))
    )
    (net (code "47") (name "unconnected-(J1C-Pad4)") (class "Default")
      (node (ref "J1C") (pin "4") (pinfunction "4_4") (pintype "passive"))
    )
  )
)
